# MultiVS_7x.net
KiCad netlist of a schematic drawn in EAGLE
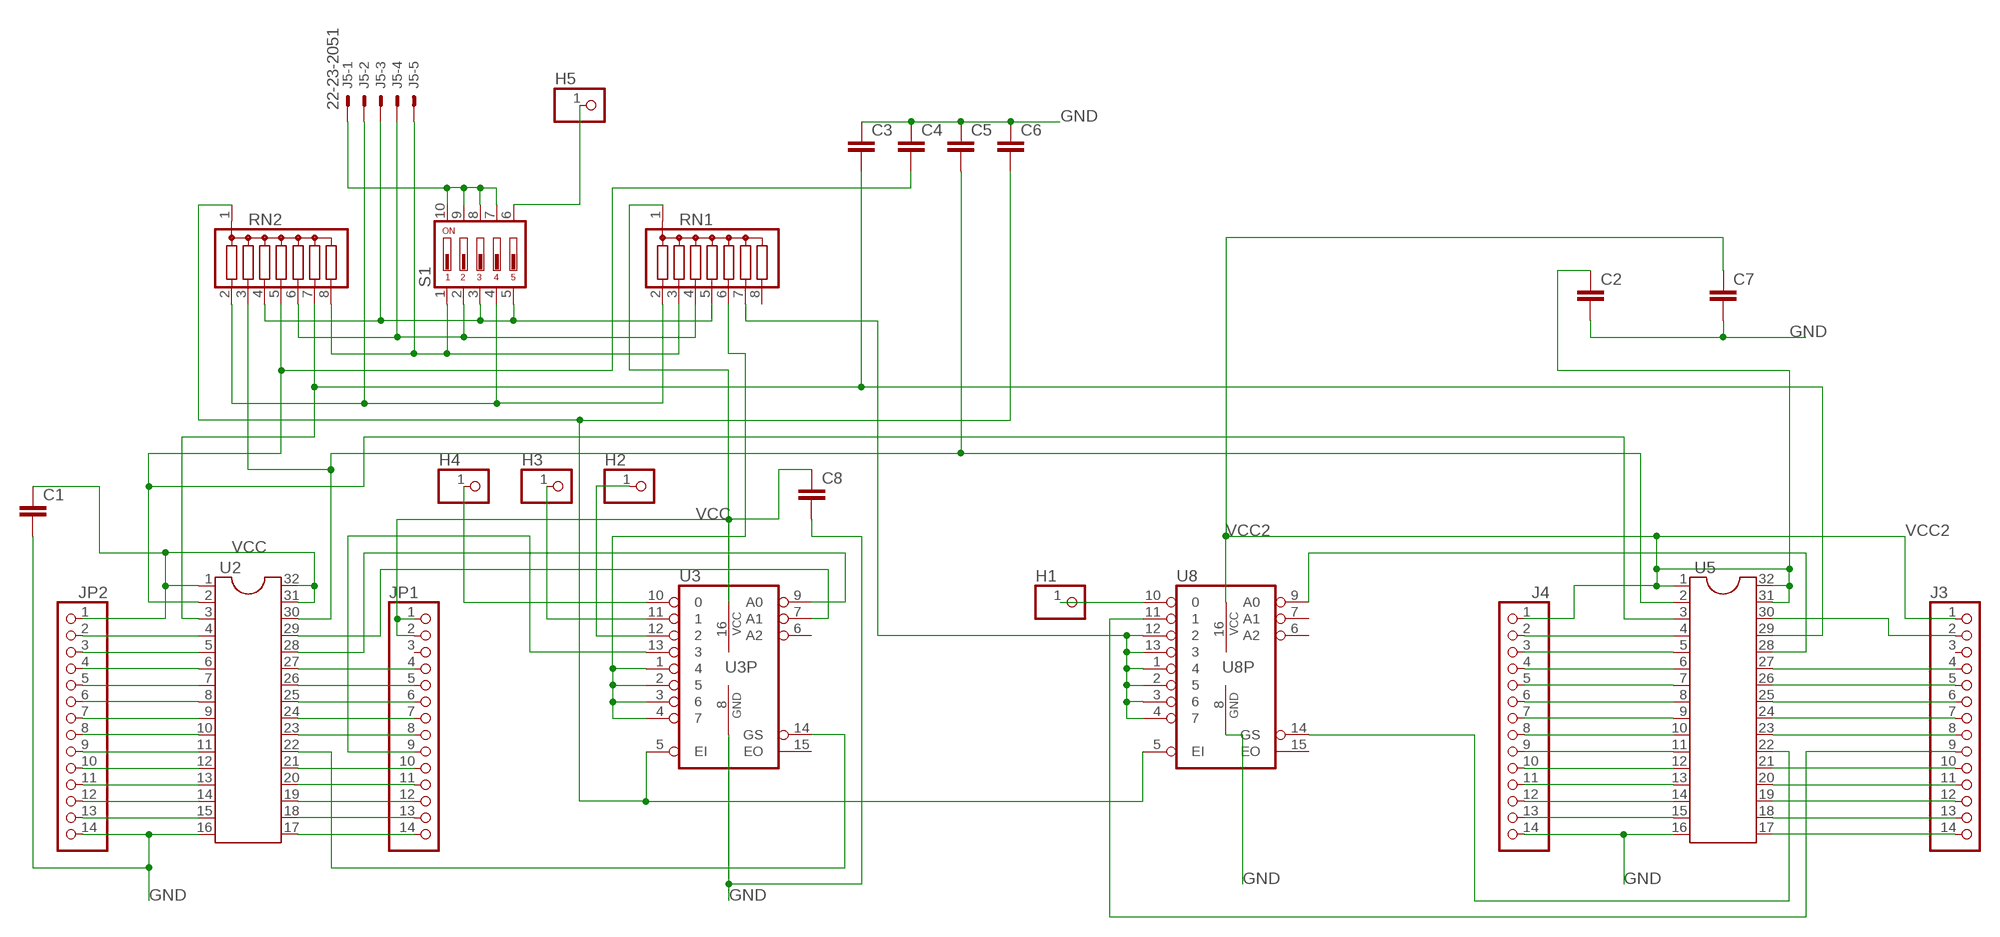
[diagram p0: schematic, sheet 1]

(export (version "E")
  (design (tool "Eeschema 10.0.6"))
  (components
    (comp (ref "C1")
      (value "C2.5/4")
      (footprint "eagle-import:C2.5-4")
      (libsource (lib "eagle-import") (part "C2.5/4"))
    )
    (comp (ref "C2")
      (value "C2.5/4")
      (footprint "eagle-import:C2.5-4")
      (libsource (lib "eagle-import") (part "C2.5/4"))
    )
    (comp (ref "C3")
      (value "C2.5/4")
      (footprint "eagle-import:C2.5-4")
      (libsource (lib "eagle-import") (part "C2.5/4"))
    )
    (comp (ref "C4")
      (value "C2.5/4")
      (footprint "eagle-import:C2.5-4")
      (libsource (lib "eagle-import") (part "C2.5/4"))
    )
    (comp (ref "C5")
      (value "C2.5/4")
      (footprint "eagle-import:C2.5-4")
      (libsource (lib "eagle-import") (part "C2.5/4"))
    )
    (comp (ref "C6")
      (value "C2.5/4")
      (footprint "eagle-import:C2.5-4")
      (libsource (lib "eagle-import") (part "C2.5/4"))
    )
    (comp (ref "C7")
      (value "C2.5/4")
      (footprint "eagle-import:C2.5-4")
      (libsource (lib "eagle-import") (part "C2.5/4"))
    )
    (comp (ref "C8")
      (value "C2.5/4")
      (footprint "eagle-import:C2.5-4")
      (libsource (lib "eagle-import") (part "C2.5/4"))
    )
    (comp (ref "H1")
      (value "PINHD-1X1")
      (footprint "eagle-import:1X01")
      (libsource (lib "eagle-import") (part "PINHD-1X1"))
    )
    (comp (ref "H2")
      (value "PINHD-1X1")
      (footprint "eagle-import:1X01")
      (libsource (lib "eagle-import") (part "PINHD-1X1"))
    )
    (comp (ref "H3")
      (value "PINHD-1X1")
      (footprint "eagle-import:1X01")
      (libsource (lib "eagle-import") (part "PINHD-1X1"))
    )
    (comp (ref "H4")
      (value "PINHD-1X1")
      (footprint "eagle-import:1X01")
      (libsource (lib "eagle-import") (part "PINHD-1X1"))
    )
    (comp (ref "H5")
      (value "PINHD-1X1")
      (footprint "eagle-import:1X01")
      (libsource (lib "eagle-import") (part "PINHD-1X1"))
    )
    (comp (ref "J3")
      (value "PINHD-1X14")
      (footprint "eagle-import:1X14")
      (libsource (lib "eagle-import") (part "PINHD-1X14"))
    )
    (comp (ref "J4")
      (value "PINHD-1X14")
      (footprint "eagle-import:1X14")
      (libsource (lib "eagle-import") (part "PINHD-1X14"))
    )
    (comp (ref "J5")
      (value "22-23-2051")
      (footprint "eagle-import:22-23-2051")
      (fields (field (name "MF") "MOLEX"))
      (libsource (lib "eagle-import") (part "22-23-2051"))
    )
    (comp (ref "JP1")
      (value "PINHD-1X14")
      (footprint "eagle-import:1X14")
      (libsource (lib "eagle-import") (part "PINHD-1X14"))
    )
    (comp (ref "JP2")
      (value "PINHD-1X14")
      (footprint "eagle-import:1X14")
      (libsource (lib "eagle-import") (part "PINHD-1X14"))
    )
    (comp (ref "RN1")
      (value "G07R")
      (footprint "eagle-import:SIL8")
      (libsource (lib "eagle-import") (part "G07R"))
    )
    (comp (ref "RN2")
      (value "G07R")
      (footprint "eagle-import:SIL8")
      (libsource (lib "eagle-import") (part "G07R"))
    )
    (comp (ref "S1")
      (value "DIP05YL")
      (footprint "eagle-import:DIP05YL")
      (libsource (lib "eagle-import") (part "DIP05YL"))
    )
    (comp (ref "U2")
      (value "DIL32")
      (footprint "eagle-import:DIL32")
      (libsource (lib "eagle-import") (part "DIL32"))
    )
    (comp (ref "U3")
      (value "74LS148N")
      (footprint "eagle-import:DIL16")
      (libsource (lib "eagle-import") (part "74148NLS"))
    )
    (comp (ref "U5")
      (value "DIL32")
      (footprint "eagle-import:DIL32")
      (libsource (lib "eagle-import") (part "DIL32"))
    )
    (comp (ref "U8")
      (value "74LS148N")
      (footprint "eagle-import:DIL16")
      (libsource (lib "eagle-import") (part "74148NLS"))
    )
  )
  (nets
    (net (code "1") (name "/GND") (class "Default")
      (node (ref "C1") (pin "2") (pinfunction "2_2") (pintype "passive"))
      (node (ref "C2") (pin "2") (pinfunction "2_2") (pintype "passive"))
      (node (ref "C3") (pin "1") (pinfunction "1_1") (pintype "passive"))
      (node (ref "C4") (pin "1") (pinfunction "1_1") (pintype "passive"))
      (node (ref "C5") (pin "1") (pinfunction "1_1") (pintype "passive"))
      (node (ref "C6") (pin "1") (pinfunction "1_1") (pintype "passive"))
      (node (ref "C7") (pin "2") (pinfunction "2_2") (pintype "passive"))
      (node (ref "C8") (pin "2") (pinfunction "2_2") (pintype "passive"))
      (node (ref "J4") (pin "14") (pinfunction "14_14") (pintype "passive"))
      (node (ref "JP2") (pin "14") (pinfunction "14_14") (pintype "passive"))
      (node (ref "U2") (pin "16") (pinfunction "16_16") (pintype "passive"))
      (node (ref "U3") (pin "8") (pinfunction "GND_8") (pintype "power_in"))
      (node (ref "U5") (pin "16") (pinfunction "16_16") (pintype "passive"))
      (node (ref "U8") (pin "8") (pinfunction "GND_8") (pintype "power_in"))
    )
    (net (code "2") (name "/VCC") (class "Default")
      (node (ref "C1") (pin "1") (pinfunction "1_1") (pintype "passive"))
      (node (ref "C8") (pin "1") (pinfunction "1_1") (pintype "passive"))
      (node (ref "JP1") (pin "1") (pinfunction "1_1") (pintype "passive"))
      (node (ref "JP1") (pin "2") (pinfunction "2_2") (pintype "passive"))
      (node (ref "JP2") (pin "1") (pinfunction "1_1") (pintype "passive"))
      (node (ref "RN1") (pin "1") (pinfunction "1_1") (pintype "passive"))
      (node (ref "U2") (pin "1") (pinfunction "1_1") (pintype "passive"))
      (node (ref "U2") (pin "31") (pinfunction "31_31") (pintype "passive"))
      (node (ref "U2") (pin "32") (pinfunction "32_32") (pintype "passive"))
      (node (ref "U3") (pin "16") (pinfunction "VCC_16") (pintype "power_in"))
    )
    (net (code "3") (name "/VCC2") (class "Default")
      (node (ref "C2") (pin "1") (pinfunction "1_1") (pintype "passive"))
      (node (ref "C7") (pin "1") (pinfunction "1_1") (pintype "passive"))
      (node (ref "J3") (pin "1") (pinfunction "1_1") (pintype "passive"))
      (node (ref "J4") (pin "1") (pinfunction "1_1") (pintype "passive"))
      (node (ref "U5") (pin "1") (pinfunction "1_1") (pintype "passive"))
      (node (ref "U5") (pin "31") (pinfunction "31_31") (pintype "passive"))
      (node (ref "U5") (pin "32") (pinfunction "32_32") (pintype "passive"))
      (node (ref "U8") (pin "16") (pinfunction "VCC_16") (pintype "power_in"))
    )
    (net (code "4") (name "Net-(C3-Pad2)") (class "Default")
      (node (ref "C3") (pin "2") (pinfunction "2_2") (pintype "passive"))
      (node (ref "RN2") (pin "7") (pinfunction "7_7") (pintype "passive"))
      (node (ref "U2") (pin "3") (pinfunction "3_3") (pintype "passive"))
      (node (ref "U5") (pin "29") (pinfunction "29_29") (pintype "passive"))
    )
    (net (code "5") (name "Net-(C4-Pad2)") (class "Default")
      (node (ref "C4") (pin "2") (pinfunction "2_2") (pintype "passive"))
      (node (ref "RN2") (pin "5") (pinfunction "5_5") (pintype "passive"))
      (node (ref "U2") (pin "2") (pinfunction "2_2") (pintype "passive"))
      (node (ref "U5") (pin "3") (pinfunction "3_3") (pintype "passive"))
    )
    (net (code "6") (name "Net-(C5-Pad2)") (class "Default")
      (node (ref "C5") (pin "2") (pinfunction "2_2") (pintype "passive"))
      (node (ref "RN2") (pin "3") (pinfunction "3_3") (pintype "passive"))
      (node (ref "U2") (pin "30") (pinfunction "30_30") (pintype "passive"))
      (node (ref "U5") (pin "2") (pinfunction "2_2") (pintype "passive"))
    )
    (net (code "7") (name "Net-(H5-Pad1)") (class "Default")
      (node (ref "H5") (pin "1") (pinfunction "1_1") (pintype "passive"))
      (node (ref "S1") (pin "6") (pinfunction "6_6") (pintype "passive"))
    )
    (net (code "8") (name "Net-(J3-Pad2)") (class "Default")
      (node (ref "J3") (pin "2") (pinfunction "2_2") (pintype "passive"))
      (node (ref "U5") (pin "30") (pinfunction "30_30") (pintype "passive"))
    )
    (net (code "9") (name "Net-(J3-Pad4)") (class "Default")
      (node (ref "J3") (pin "4") (pinfunction "4_4") (pintype "passive"))
      (node (ref "U5") (pin "27") (pinfunction "27_27") (pintype "passive"))
    )
    (net (code "10") (name "Net-(J3-Pad5)") (class "Default")
      (node (ref "J3") (pin "5") (pinfunction "5_5") (pintype "passive"))
      (node (ref "U5") (pin "26") (pinfunction "26_26") (pintype "passive"))
    )
    (net (code "11") (name "Net-(J3-Pad6)") (class "Default")
      (node (ref "J3") (pin "6") (pinfunction "6_6") (pintype "passive"))
      (node (ref "U5") (pin "25") (pinfunction "25_25") (pintype "passive"))
    )
    (net (code "12") (name "Net-(J3-Pad7)") (class "Default")
      (node (ref "J3") (pin "7") (pinfunction "7_7") (pintype "passive"))
      (node (ref "U5") (pin "24") (pinfunction "24_24") (pintype "passive"))
    )
    (net (code "13") (name "Net-(J3-Pad8)") (class "Default")
      (node (ref "J3") (pin "8") (pinfunction "8_8") (pintype "passive"))
      (node (ref "U5") (pin "23") (pinfunction "23_23") (pintype "passive"))
    )
    (net (code "14") (name "Net-(J3-Pad10)") (class "Default")
      (node (ref "J3") (pin "10") (pinfunction "10_10") (pintype "passive"))
      (node (ref "U5") (pin "21") (pinfunction "21_21") (pintype "passive"))
    )
    (net (code "15") (name "Net-(J3-Pad11)") (class "Default")
      (node (ref "J3") (pin "11") (pinfunction "11_11") (pintype "passive"))
      (node (ref "U5") (pin "20") (pinfunction "20_20") (pintype "passive"))
    )
    (net (code "16") (name "Net-(J3-Pad12)") (class "Default")
      (node (ref "J3") (pin "12") (pinfunction "12_12") (pintype "passive"))
      (node (ref "U5") (pin "19") (pinfunction "19_19") (pintype "passive"))
    )
    (net (code "17") (name "Net-(J3-Pad13)") (class "Default")
      (node (ref "J3") (pin "13") (pinfunction "13_13") (pintype "passive"))
      (node (ref "U5") (pin "18") (pinfunction "18_18") (pintype "passive"))
    )
    (net (code "18") (name "Net-(J3-Pad14)") (class "Default")
      (node (ref "J3") (pin "14") (pinfunction "14_14") (pintype "passive"))
      (node (ref "U5") (pin "17") (pinfunction "17_17") (pintype "passive"))
    )
    (net (code "19") (name "Net-(J4-Pad2)") (class "Default")
      (node (ref "J4") (pin "2") (pinfunction "2_2") (pintype "passive"))
      (node (ref "U5") (pin "4") (pinfunction "4_4") (pintype "passive"))
    )
    (net (code "20") (name "Net-(J4-Pad3)") (class "Default")
      (node (ref "J4") (pin "3") (pinfunction "3_3") (pintype "passive"))
      (node (ref "U5") (pin "5") (pinfunction "5_5") (pintype "passive"))
    )
    (net (code "21") (name "Net-(J4-Pad4)") (class "Default")
      (node (ref "J4") (pin "4") (pinfunction "4_4") (pintype "passive"))
      (node (ref "U5") (pin "6") (pinfunction "6_6") (pintype "passive"))
    )
    (net (code "22") (name "Net-(J4-Pad5)") (class "Default")
      (node (ref "J4") (pin "5") (pinfunction "5_5") (pintype "passive"))
      (node (ref "U5") (pin "7") (pinfunction "7_7") (pintype "passive"))
    )
    (net (code "23") (name "Net-(J4-Pad6)") (class "Default")
      (node (ref "J4") (pin "6") (pinfunction "6_6") (pintype "passive"))
      (node (ref "U5") (pin "8") (pinfunction "8_8") (pintype "passive"))
    )
    (net (code "24") (name "Net-(J4-Pad7)") (class "Default")
      (node (ref "J4") (pin "7") (pinfunction "7_7") (pintype "passive"))
      (node (ref "U5") (pin "9") (pinfunction "9_9") (pintype "passive"))
    )
    (net (code "25") (name "Net-(J4-Pad8)") (class "Default")
      (node (ref "J4") (pin "8") (pinfunction "8_8") (pintype "passive"))
      (node (ref "U5") (pin "10") (pinfunction "10_10") (pintype "passive"))
    )
    (net (code "26") (name "Net-(J4-Pad9)") (class "Default")
      (node (ref "J4") (pin "9") (pinfunction "9_9") (pintype "passive"))
      (node (ref "U5") (pin "11") (pinfunction "11_11") (pintype "passive"))
    )
    (net (code "27") (name "Net-(J4-Pad10)") (class "Default")
      (node (ref "J4") (pin "10") (pinfunction "10_10") (pintype "passive"))
      (node (ref "U5") (pin "12") (pinfunction "12_12") (pintype "passive"))
    )
    (net (code "28") (name "Net-(J4-Pad11)") (class "Default")
      (node (ref "J4") (pin "11") (pinfunction "11_11") (pintype "passive"))
      (node (ref "U5") (pin "13") (pinfunction "13_13") (pintype "passive"))
    )
    (net (code "29") (name "Net-(J4-Pad12)") (class "Default")
      (node (ref "J4") (pin "12") (pinfunction "12_12") (pintype "passive"))
      (node (ref "U5") (pin "14") (pinfunction "14_14") (pintype "passive"))
    )
    (net (code "30") (name "Net-(J4-Pad13)") (class "Default")
      (node (ref "J4") (pin "13") (pinfunction "13_13") (pintype "passive"))
      (node (ref "U5") (pin "15") (pinfunction "15_15") (pintype "passive"))
    )
    (net (code "31") (name "Net-(J5A-S)") (class "Default")
      (node (ref "J5") (pin "1") (pinfunction "S_1") (pintype "passive"))
      (node (ref "S1") (pin "10") (pinfunction "10_10") (pintype "passive"))
      (node (ref "S1") (pin "7") (pinfunction "7_7") (pintype "passive"))
      (node (ref "S1") (pin "8") (pinfunction "8_8") (pintype "passive"))
      (node (ref "S1") (pin "9") (pinfunction "9_9") (pintype "passive"))
    )
    (net (code "32") (name "Net-(J5B-S)") (class "Default")
      (node (ref "J5") (pin "2") (pinfunction "S_2") (pintype "passive"))
      (node (ref "RN1") (pin "2") (pinfunction "2_2") (pintype "passive"))
      (node (ref "RN2") (pin "2") (pinfunction "2_2") (pintype "passive"))
      (node (ref "S1") (pin "4") (pinfunction "4_4") (pintype "passive"))
    )
    (net (code "33") (name "Net-(J5C-S)") (class "Default")
      (node (ref "J5") (pin "3") (pinfunction "S_3") (pintype "passive"))
      (node (ref "RN1") (pin "5") (pinfunction "5_5") (pintype "passive"))
      (node (ref "RN2") (pin "4") (pinfunction "4_4") (pintype "passive"))
      (node (ref "S1") (pin "3") (pinfunction "3_3") (pintype "passive"))
      (node (ref "S1") (pin "5") (pinfunction "5_5") (pintype "passive"))
    )
    (net (code "34") (name "Net-(J5D-S)") (class "Default")
      (node (ref "J5") (pin "4") (pinfunction "S_4") (pintype "passive"))
      (node (ref "RN1") (pin "4") (pinfunction "4_4") (pintype "passive"))
      (node (ref "RN2") (pin "6") (pinfunction "6_6") (pintype "passive"))
      (node (ref "S1") (pin "2") (pinfunction "2_2") (pintype "passive"))
    )
    (net (code "35") (name "Net-(J5E-S)") (class "Default")
      (node (ref "J5") (pin "5") (pinfunction "S_5") (pintype "passive"))
      (node (ref "RN1") (pin "3") (pinfunction "3_3") (pintype "passive"))
      (node (ref "RN2") (pin "8") (pinfunction "8_8") (pintype "passive"))
      (node (ref "S1") (pin "1") (pinfunction "1_1") (pintype "passive"))
    )
    (net (code "36") (name "Net-(JP1-Pad4)") (class "Default")
      (node (ref "JP1") (pin "4") (pinfunction "4_4") (pintype "passive"))
      (node (ref "U2") (pin "27") (pinfunction "27_27") (pintype "passive"))
    )
    (net (code "37") (name "Net-(JP1-Pad5)") (class "Default")
      (node (ref "JP1") (pin "5") (pinfunction "5_5") (pintype "passive"))
      (node (ref "U2") (pin "26") (pinfunction "26_26") (pintype "passive"))
    )
    (net (code "38") (name "Net-(JP1-Pad6)") (class "Default")
      (node (ref "JP1") (pin "6") (pinfunction "6_6") (pintype "passive"))
      (node (ref "U2") (pin "25") (pinfunction "25_25") (pintype "passive"))
    )
    (net (code "39") (name "Net-(JP1-Pad7)") (class "Default")
      (node (ref "JP1") (pin "7") (pinfunction "7_7") (pintype "passive"))
      (node (ref "U2") (pin "24") (pinfunction "24_24") (pintype "passive"))
    )
    (net (code "40") (name "Net-(JP1-Pad8)") (class "Default")
      (node (ref "JP1") (pin "8") (pinfunction "8_8") (pintype "passive"))
      (node (ref "U2") (pin "23") (pinfunction "23_23") (pintype "passive"))
    )
    (net (code "41") (name "Net-(JP1-Pad10)") (class "Default")
      (node (ref "JP1") (pin "10") (pinfunction "10_10") (pintype "passive"))
      (node (ref "U2") (pin "21") (pinfunction "21_21") (pintype "passive"))
    )
    (net (code "42") (name "Net-(JP1-Pad11)") (class "Default")
      (node (ref "JP1") (pin "11") (pinfunction "11_11") (pintype "passive"))
      (node (ref "U2") (pin "20") (pinfunction "20_20") (pintype "passive"))
    )
    (net (code "43") (name "Net-(JP1-Pad12)") (class "Default")
      (node (ref "JP1") (pin "12") (pinfunction "12_12") (pintype "passive"))
      (node (ref "U2") (pin "19") (pinfunction "19_19") (pintype "passive"))
    )
    (net (code "44") (name "Net-(JP1-Pad13)") (class "Default")
      (node (ref "JP1") (pin "13") (pinfunction "13_13") (pintype "passive"))
      (node (ref "U2") (pin "18") (pinfunction "18_18") (pintype "passive"))
    )
    (net (code "45") (name "Net-(JP1-Pad14)") (class "Default")
      (node (ref "JP1") (pin "14") (pinfunction "14_14") (pintype "passive"))
      (node (ref "U2") (pin "17") (pinfunction "17_17") (pintype "passive"))
    )
    (net (code "46") (name "Net-(JP2-Pad2)") (class "Default")
      (node (ref "JP2") (pin "2") (pinfunction "2_2") (pintype "passive"))
      (node (ref "U2") (pin "4") (pinfunction "4_4") (pintype "passive"))
    )
    (net (code "47") (name "Net-(JP2-Pad3)") (class "Default")
      (node (ref "JP2") (pin "3") (pinfunction "3_3") (pintype "passive"))
      (node (ref "U2") (pin "5") (pinfunction "5_5") (pintype "passive"))
    )
    (net (code "48") (name "Net-(JP2-Pad4)") (class "Default")
      (node (ref "JP2") (pin "4") (pinfunction "4_4") (pintype "passive"))
      (node (ref "U2") (pin "6") (pinfunction "6_6") (pintype "passive"))
    )
    (net (code "49") (name "Net-(JP2-Pad5)") (class "Default")
      (node (ref "JP2") (pin "5") (pinfunction "5_5") (pintype "passive"))
      (node (ref "U2") (pin "7") (pinfunction "7_7") (pintype "passive"))
    )
    (net (code "50") (name "Net-(JP2-Pad6)") (class "Default")
      (node (ref "JP2") (pin "6") (pinfunction "6_6") (pintype "passive"))
      (node (ref "U2") (pin "8") (pinfunction "8_8") (pintype "passive"))
    )
    (net (code "51") (name "Net-(JP2-Pad7)") (class "Default")
      (node (ref "JP2") (pin "7") (pinfunction "7_7") (pintype "passive"))
      (node (ref "U2") (pin "9") (pinfunction "9_9") (pintype "passive"))
    )
    (net (code "52") (name "Net-(JP2-Pad8)") (class "Default")
      (node (ref "JP2") (pin "8") (pinfunction "8_8") (pintype "passive"))
      (node (ref "U2") (pin "10") (pinfunction "10_10") (pintype "passive"))
    )
    (net (code "53") (name "Net-(JP2-Pad9)") (class "Default")
      (node (ref "JP2") (pin "9") (pinfunction "9_9") (pintype "passive"))
      (node (ref "U2") (pin "11") (pinfunction "11_11") (pintype "passive"))
    )
    (net (code "54") (name "Net-(JP2-Pad10)") (class "Default")
      (node (ref "JP2") (pin "10") (pinfunction "10_10") (pintype "passive"))
      (node (ref "U2") (pin "12") (pinfunction "12_12") (pintype "passive"))
    )
    (net (code "55") (name "Net-(JP2-Pad11)") (class "Default")
      (node (ref "JP2") (pin "11") (pinfunction "11_11") (pintype "passive"))
      (node (ref "U2") (pin "13") (pinfunction "13_13") (pintype "passive"))
    )
    (net (code "56") (name "Net-(JP2-Pad12)") (class "Default")
      (node (ref "JP2") (pin "12") (pinfunction "12_12") (pintype "passive"))
      (node (ref "U2") (pin "14") (pinfunction "14_14") (pintype "passive"))
    )
    (net (code "57") (name "Net-(JP2-Pad13)") (class "Default")
      (node (ref "JP2") (pin "13") (pinfunction "13_13") (pintype "passive"))
      (node (ref "U2") (pin "15") (pinfunction "15_15") (pintype "passive"))
    )
    (net (code "58") (name "Net-(U3A-0)") (class "Default")
      (node (ref "H4") (pin "1") (pinfunction "1_1") (pintype "passive"))
      (node (ref "U3") (pin "10") (pinfunction "0_10") (pintype "input"))
    )
    (net (code "59") (name "Net-(U3A-1)") (class "Default")
      (node (ref "H3") (pin "1") (pinfunction "1_1") (pintype "passive"))
      (node (ref "U3") (pin "11") (pinfunction "1_11") (pintype "input"))
    )
    (net (code "60") (name "Net-(U3A-2)") (class "Default")
      (node (ref "H2") (pin "1") (pinfunction "1_1") (pintype "passive"))
      (node (ref "U3") (pin "12") (pinfunction "2_12") (pintype "input"))
    )
    (net (code "61") (name "Net-(U3A-3)") (class "Default")
      (node (ref "JP1") (pin "9") (pinfunction "9_9") (pintype "passive"))
      (node (ref "U3") (pin "13") (pinfunction "3_13") (pintype "input"))
    )
    (net (code "62") (name "Net-(U3A-4)") (class "Default")
      (node (ref "RN1") (pin "6") (pinfunction "6_6") (pintype "passive"))
      (node (ref "U3") (pin "1") (pinfunction "4_1") (pintype "input"))
      (node (ref "U3") (pin "2") (pinfunction "5_2") (pintype "input"))
      (node (ref "U3") (pin "3") (pinfunction "6_3") (pintype "input"))
      (node (ref "U3") (pin "4") (pinfunction "7_4") (pintype "input"))
    )
    (net (code "63") (name "Net-(U3A-A0)") (class "Default")
      (node (ref "U2") (pin "28") (pinfunction "28_28") (pintype "passive"))
      (node (ref "U3") (pin "9") (pinfunction "A0_9") (pintype "output"))
    )
    (net (code "64") (name "Net-(U3A-A1)") (class "Default")
      (node (ref "U2") (pin "29") (pinfunction "29_29") (pintype "passive"))
      (node (ref "U3") (pin "7") (pinfunction "A1_7") (pintype "output"))
    )
    (net (code "65") (name "Net-(U3A-EI)") (class "Default")
      (node (ref "C6") (pin "2") (pinfunction "2_2") (pintype "passive"))
      (node (ref "RN2") (pin "1") (pinfunction "1_1") (pintype "passive"))
      (node (ref "U3") (pin "5") (pinfunction "EI_5") (pintype "input"))
      (node (ref "U8") (pin "5") (pinfunction "EI_5") (pintype "input"))
    )
    (net (code "66") (name "Net-(U3A-GS)") (class "Default")
      (node (ref "U2") (pin "22") (pinfunction "22_22") (pintype "passive"))
      (node (ref "U3") (pin "14") (pinfunction "GS_14") (pintype "output"))
    )
    (net (code "67") (name "Net-(U8A-0)") (class "Default")
      (node (ref "H1") (pin "1") (pinfunction "1_1") (pintype "passive"))
      (node (ref "U8") (pin "10") (pinfunction "0_10") (pintype "input"))
    )
    (net (code "68") (name "Net-(U8A-1)") (class "Default")
      (node (ref "J3") (pin "9") (pinfunction "9_9") (pintype "passive"))
      (node (ref "U8") (pin "11") (pinfunction "1_11") (pintype "input"))
    )
    (net (code "69") (name "Net-(U8A-2)") (class "Default")
      (node (ref "RN1") (pin "7") (pinfunction "7_7") (pintype "passive"))
      (node (ref "U8") (pin "1") (pinfunction "4_1") (pintype "input"))
      (node (ref "U8") (pin "12") (pinfunction "2_12") (pintype "input"))
      (node (ref "U8") (pin "13") (pinfunction "3_13") (pintype "input"))
      (node (ref "U8") (pin "2") (pinfunction "5_2") (pintype "input"))
      (node (ref "U8") (pin "3") (pinfunction "6_3") (pintype "input"))
      (node (ref "U8") (pin "4") (pinfunction "7_4") (pintype "input"))
    )
    (net (code "70") (name "Net-(U8A-A0)") (class "Default")
      (node (ref "U5") (pin "28") (pinfunction "28_28") (pintype "passive"))
      (node (ref "U8") (pin "9") (pinfunction "A0_9") (pintype "output"))
    )
    (net (code "71") (name "Net-(U8A-GS)") (class "Default")
      (node (ref "U5") (pin "22") (pinfunction "22_22") (pintype "passive"))
      (node (ref "U8") (pin "14") (pinfunction "GS_14") (pintype "output"))
    )
    (net (code "72") (name "unconnected-(J3-Pad3)") (class "Default")
      (node (ref "J3") (pin "3") (pinfunction "3_3") (pintype "passive"))
    )
    (net (code "73") (name "unconnected-(JP1-Pad3)") (class "Default")
      (node (ref "JP1") (pin "3") (pinfunction "3_3") (pintype "passive"))
    )
    (net (code "74") (name "unconnected-(RN1-Pad8)") (class "Default")
      (node (ref "RN1") (pin "8") (pinfunction "8_8") (pintype "passive"))
    )
    (net (code "75") (name "unconnected-(U3A-A2-Pad6)") (class "Default")
      (node (ref "U3") (pin "6") (pinfunction "A2_6") (pintype "output"))
    )
    (net (code "76") (name "unconnected-(U3A-EO-Pad15)") (class "Default")
      (node (ref "U3") (pin "15") (pinfunction "EO_15") (pintype "output"))
    )
    (net (code "77") (name "unconnected-(U8A-A1-Pad7)") (class "Default")
      (node (ref "U8") (pin "7") (pinfunction "A1_7") (pintype "output"))
    )
    (net (code "78") (name "unconnected-(U8A-A2-Pad6)") (class "Default")
      (node (ref "U8") (pin "6") (pinfunction "A2_6") (pintype "output"))
    )
    (net (code "79") (name "unconnected-(U8A-EO-Pad15)") (class "Default")
      (node (ref "U8") (pin "15") (pinfunction "EO_15") (pintype "output"))
    )
  )
)
